# 1.net
KiCad netlist of a schematic drawn in Altium Designer
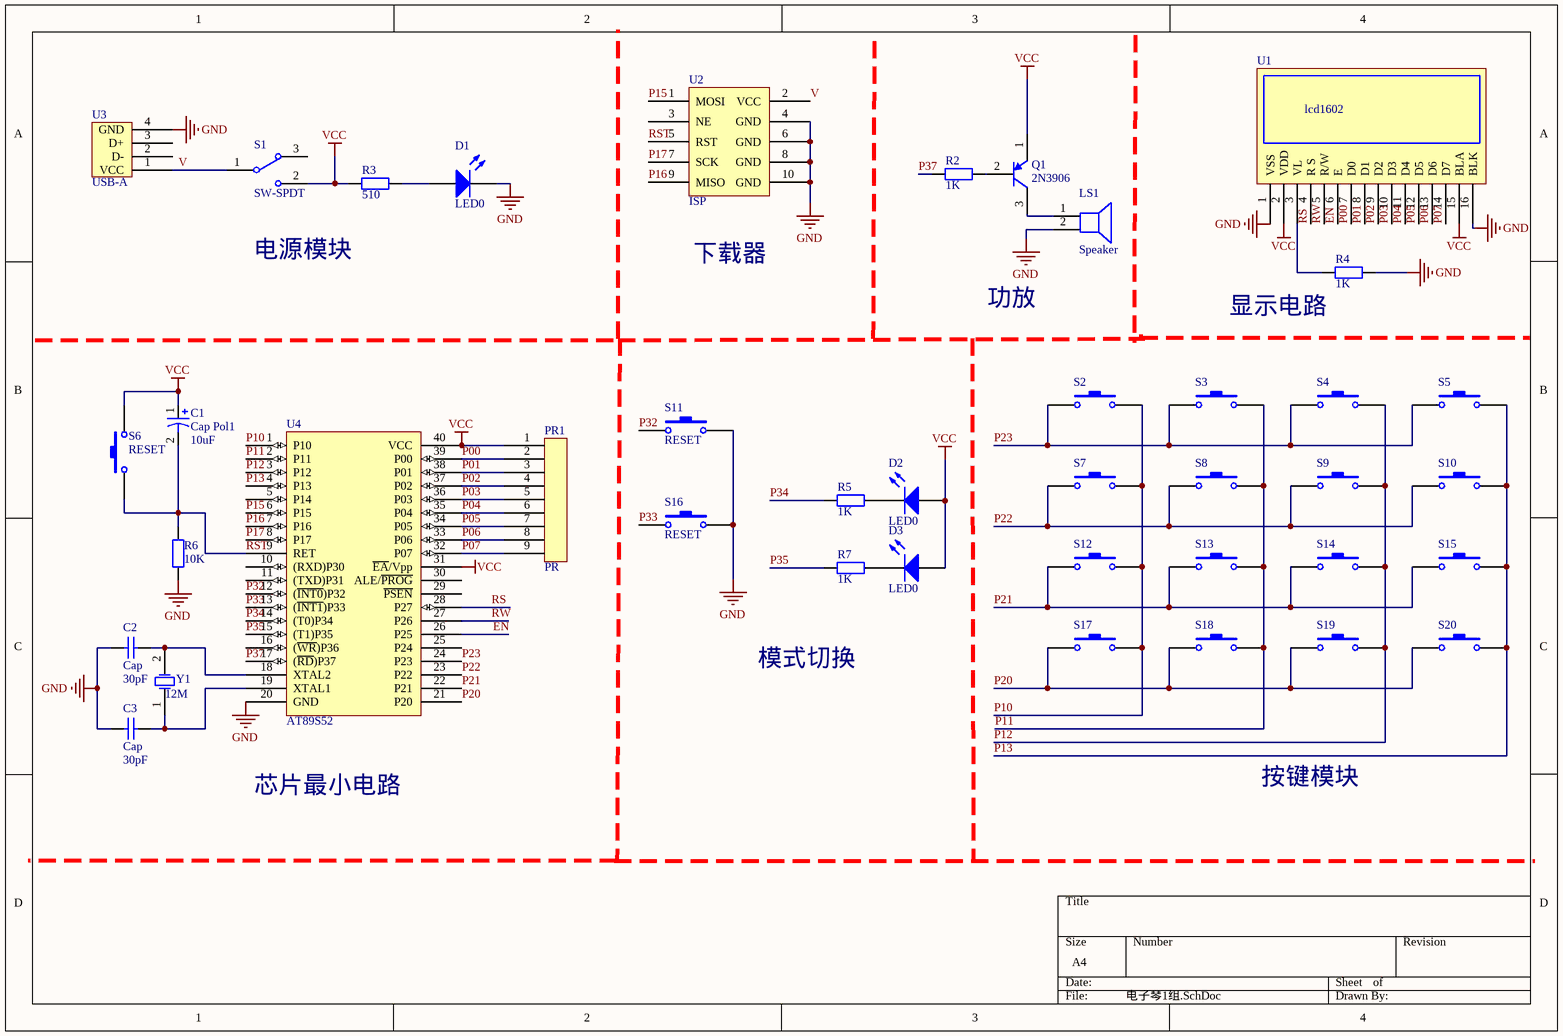
[diagram p0: 电子琴1组.SchDoc]

(export (version "E")
  (design (tool "Eeschema 10.0.6"))
  (components
    (comp (ref "C1")
      (value "Cap Pol1")
      (footprint "RB0.1")
      (description "Polarized Capacitor (Radial)")
      (fields (field (name "ALTIUM_VALUE") "10uF") (field (name "PUBLISHER") "Altium Limited"))
      (libsource (lib "schlib1-D") (part "Cap Pol1"))
    )
    (comp (ref "C2")
      (value "Cap")
      (footprint "RAD-0.1")
      (description "Capacitor")
      (fields (field (name "ALTIUM_VALUE") "30pF") (field (name "PUBLISHER") "Altium Limited"))
      (libsource (lib "schlib1-D") (part "Cap"))
    )
    (comp (ref "C3")
      (value "Cap")
      (footprint "RAD-0.1")
      (description "Capacitor")
      (fields (field (name "ALTIUM_VALUE") "30pF") (field (name "PUBLISHER") "Altium Limited"))
      (libsource (lib "schlib1-D") (part "Cap"))
    )
    (comp (ref "D1")
      (value "LED0")
      (footprint "RB0.1")
      (description "Typical INFRARED GaAs LED")
      (fields (field (name "PUBLISHER") "Altium Limited"))
      (libsource (lib "schlib1-D") (part "LED0"))
    )
    (comp (ref "D2")
      (value "LED0")
      (footprint "RB0.1")
      (description "Typical INFRARED GaAs LED")
      (fields (field (name "PUBLISHER") "Altium Limited"))
      (libsource (lib "schlib1-D") (part "LED0"))
    )
    (comp (ref "D3")
      (value "LED0")
      (footprint "RB0.1")
      (description "Typical INFRARED GaAs LED")
      (fields (field (name "PUBLISHER") "Altium Limited"))
      (libsource (lib "schlib1-D") (part "LED0"))
    )
    (comp (ref "LS1")
      (value "Speaker")
      (footprint "Speaker")
      (description "Loudspeaker")
      (fields (field (name "PUBLISHER") "Altium Limited"))
      (libsource (lib "schlib1-D") (part "Speaker"))
    )
    (comp (ref "PR1") (value "PR") (footprint "SIP9") (libsource (lib "Schlib1-4-22") (part "PR")))
    (comp (ref "Q1")
      (value "2N3906")
      (footprint "TO-92-M")
      (description "PNP General Purpose Amplifier")
      (fields (field (name "PUBLISHER") "Altium Limited"))
      (libsource (lib "schlib1-D") (part "2N3906"))
    )
    (comp (ref "R2")
      (value "1K")
      (footprint "AXIAL-0.3")
      (description "Resistor")
      (fields (field (name "PUBLISHER") "Altium Limited"))
      (libsource (lib "") (part "Res2_2"))
    )
    (comp (ref "R3")
      (value "510")
      (footprint "AXIAL-0.3")
      (description "Resistor")
      (fields (field (name "PUBLISHER") "Altium Limited"))
      (libsource (lib "schlib1-D") (part "Res2"))
    )
    (comp (ref "R4")
      (value "1K")
      (footprint "AXIAL-0.3")
      (description "Resistor")
      (fields (field (name "PUBLISHER") "Altium Limited"))
      (libsource (lib "schlib1-D") (part "Res2"))
    )
    (comp (ref "R5")
      (value "1K")
      (footprint "AXIAL-0.3")
      (description "Resistor")
      (fields (field (name "PUBLISHER") "Altium Limited"))
      (libsource (lib "schlib1-D") (part "Res2"))
    )
    (comp (ref "R6")
      (value "10K")
      (footprint "AXIAL-0.3")
      (description "Resistor")
      (fields (field (name "PUBLISHER") "Altium Limited"))
      (libsource (lib "") (part "Res2_1"))
    )
    (comp (ref "R7")
      (value "1K")
      (footprint "AXIAL-0.3")
      (description "Resistor")
      (fields (field (name "PUBLISHER") "Altium Limited"))
      (libsource (lib "schlib1-D") (part "Res2"))
    )
    (comp (ref "S1")
      (value "SW-SPDT")
      (footprint "KEY-6 - duplicate")
      (description "SPDT Subminiature Toggle Switch, Right Angle Mounting, Vertical Actuation")
      (fields (field (name "PUBLISHER") "Altium Limited"))
      (libsource (lib "schlib1-D") (part "SW-SPDT"))
    )
    (comp (ref "S2")
      (value "~")
      (footprint "SPST6*6")
      (description "Switch")
      (fields (field (name "PUBLISHER") "Altium Limited"))
      (libsource (lib "schlib1-D") (part "SW-PB"))
    )
    (comp (ref "S3")
      (value "~")
      (footprint "SPST6*6")
      (description "Switch")
      (fields (field (name "PUBLISHER") "Altium Limited"))
      (libsource (lib "schlib1-D") (part "SW-PB"))
    )
    (comp (ref "S4")
      (value "~")
      (footprint "SPST6*6")
      (description "Switch")
      (fields (field (name "PUBLISHER") "Altium Limited"))
      (libsource (lib "schlib1-D") (part "SW-PB"))
    )
    (comp (ref "S5")
      (value "~")
      (footprint "SPST6*6")
      (description "Switch")
      (fields (field (name "PUBLISHER") "Altium Limited"))
      (libsource (lib "schlib1-D") (part "SW-PB"))
    )
    (comp (ref "S6")
      (value "RESET")
      (footprint "SPST6*6")
      (description "Switch")
      (fields (field (name "PUBLISHER") "Altium Limited"))
      (libsource (lib "schlib1-D") (part "SW-PB"))
    )
    (comp (ref "S7")
      (value "~")
      (footprint "SPST6*6")
      (description "Switch")
      (fields (field (name "PUBLISHER") "Altium Limited"))
      (libsource (lib "schlib1-D") (part "SW-PB"))
    )
    (comp (ref "S8")
      (value "~")
      (footprint "SPST6*6")
      (description "Switch")
      (fields (field (name "PUBLISHER") "Altium Limited"))
      (libsource (lib "schlib1-D") (part "SW-PB"))
    )
    (comp (ref "S9")
      (value "~")
      (footprint "SPST6*6")
      (description "Switch")
      (fields (field (name "PUBLISHER") "Altium Limited"))
      (libsource (lib "schlib1-D") (part "SW-PB"))
    )
    (comp (ref "S10")
      (value "~")
      (footprint "SPST6*6")
      (description "Switch")
      (fields (field (name "PUBLISHER") "Altium Limited"))
      (libsource (lib "schlib1-D") (part "SW-PB"))
    )
    (comp (ref "S11")
      (value "RESET")
      (footprint "SPST6*6")
      (description "Switch")
      (fields (field (name "PUBLISHER") "Altium Limited"))
      (libsource (lib "schlib1-D") (part "SW-PB"))
    )
    (comp (ref "S12")
      (value "~")
      (footprint "SPST6*6")
      (description "Switch")
      (fields (field (name "PUBLISHER") "Altium Limited"))
      (libsource (lib "schlib1-D") (part "SW-PB"))
    )
    (comp (ref "S13")
      (value "~")
      (footprint "SPST6*6")
      (description "Switch")
      (fields (field (name "PUBLISHER") "Altium Limited"))
      (libsource (lib "schlib1-D") (part "SW-PB"))
    )
    (comp (ref "S14")
      (value "~")
      (footprint "SPST6*6")
      (description "Switch")
      (fields (field (name "PUBLISHER") "Altium Limited"))
      (libsource (lib "schlib1-D") (part "SW-PB"))
    )
    (comp (ref "S15")
      (value "~")
      (footprint "SPST6*6")
      (description "Switch")
      (fields (field (name "PUBLISHER") "Altium Limited"))
      (libsource (lib "schlib1-D") (part "SW-PB"))
    )
    (comp (ref "S16")
      (value "RESET")
      (footprint "SPST6*6")
      (description "Switch")
      (fields (field (name "PUBLISHER") "Altium Limited"))
      (libsource (lib "schlib1-D") (part "SW-PB"))
    )
    (comp (ref "S17")
      (value "~")
      (footprint "SPST6*6")
      (description "Switch")
      (fields (field (name "PUBLISHER") "Altium Limited"))
      (libsource (lib "schlib1-D") (part "SW-PB"))
    )
    (comp (ref "S18")
      (value "~")
      (footprint "SPST6*6")
      (description "Switch")
      (fields (field (name "PUBLISHER") "Altium Limited"))
      (libsource (lib "schlib1-D") (part "SW-PB"))
    )
    (comp (ref "S19")
      (value "~")
      (footprint "SPST6*6")
      (description "Switch")
      (fields (field (name "PUBLISHER") "Altium Limited"))
      (libsource (lib "schlib1-D") (part "SW-PB"))
    )
    (comp (ref "S20")
      (value "~")
      (footprint "SPST6*6")
      (description "Switch")
      (fields (field (name "PUBLISHER") "Altium Limited"))
      (libsource (lib "schlib1-D") (part "SW-PB"))
    )
    (comp (ref "U1")
      (value "lcd1602")
      (footprint "LCD1602")
      (libsource (lib "Schlib LED1206") (part "lcd1602"))
    )
    (comp (ref "U2") (value "ISP") (footprint "IDC10") (libsource (lib "Schlib1-4-22") (part "ISP")))
    (comp (ref "U3") (value "USB-A") (footprint "USB_A") (libsource (lib "Schlib1-4-22") (part "USB-A")))
    (comp (ref "U4")
      (value "AT89S52")
      (footprint "DIP40_51MCU")
      (libsource (lib "Schlib1-4-22") (part "AT89S52"))
    )
    (comp (ref "Y1")
      (value "12M")
      (footprint "XTAL1")
      (description "Crystal Oscillator")
      (fields (field (name "PUBLISHER") "Altium Limited"))
      (libsource (lib "schlib1-D") (part "XTAL"))
    )
  )
  (nets
    (net (code "1") (name "/EN") (class "Default")
      (node (ref "U1") (pin "6") (pinfunction "E_6") (pintype "passive"))
      (node (ref "U4") (pin "26") (pinfunction "P25_26") (pintype "passive"))
    )
    (net (code "2") (name "/P00") (class "Default")
      (node (ref "PR1") (pin "2") (pinfunction "1_2") (pintype "passive"))
      (node (ref "U1") (pin "7") (pinfunction "D0_7") (pintype "passive"))
      (node (ref "U4") (pin "39") (pinfunction "P00_39") (pintype "bidirectional"))
    )
    (net (code "3") (name "/P01") (class "Default")
      (node (ref "PR1") (pin "3") (pinfunction "2_3") (pintype "passive"))
      (node (ref "U1") (pin "8") (pinfunction "D1_8") (pintype "passive"))
      (node (ref "U4") (pin "38") (pinfunction "P01_38") (pintype "bidirectional"))
    )
    (net (code "4") (name "/P02") (class "Default")
      (node (ref "PR1") (pin "4") (pinfunction "4_4") (pintype "passive"))
      (node (ref "U1") (pin "9") (pinfunction "D2_9") (pintype "passive"))
      (node (ref "U4") (pin "37") (pinfunction "P02_37") (pintype "bidirectional"))
    )
    (net (code "5") (name "/P03") (class "Default")
      (node (ref "PR1") (pin "5") (pinfunction "5_5") (pintype "passive"))
      (node (ref "U1") (pin "10") (pinfunction "D3_10") (pintype "passive"))
      (node (ref "U4") (pin "36") (pinfunction "P03_36") (pintype "bidirectional"))
    )
    (net (code "6") (name "/P04") (class "Default")
      (node (ref "PR1") (pin "6") (pinfunction "6_6") (pintype "passive"))
      (node (ref "U1") (pin "11") (pinfunction "D4_11") (pintype "passive"))
      (node (ref "U4") (pin "35") (pinfunction "P04_35") (pintype "bidirectional"))
    )
    (net (code "7") (name "/P05") (class "Default")
      (node (ref "PR1") (pin "7") (pinfunction "7_7") (pintype "passive"))
      (node (ref "U1") (pin "12") (pinfunction "D5_12") (pintype "passive"))
      (node (ref "U4") (pin "34") (pinfunction "P05_34") (pintype "bidirectional"))
    )
    (net (code "8") (name "/P06") (class "Default")
      (node (ref "PR1") (pin "8") (pinfunction "8_8") (pintype "passive"))
      (node (ref "U1") (pin "13") (pinfunction "D6_13") (pintype "passive"))
      (node (ref "U4") (pin "33") (pinfunction "P06_33") (pintype "bidirectional"))
    )
    (net (code "9") (name "/P07") (class "Default")
      (node (ref "PR1") (pin "9") (pinfunction "9_9") (pintype "passive"))
      (node (ref "U1") (pin "14") (pinfunction "D7_14") (pintype "passive"))
      (node (ref "U4") (pin "32") (pinfunction "P07_32") (pintype "bidirectional"))
    )
    (net (code "10") (name "/P10") (class "Default")
      (node (ref "S12") (pin "2") (pinfunction "2_2") (pintype "passive"))
      (node (ref "S17") (pin "2") (pinfunction "2_2") (pintype "passive"))
      (node (ref "S2") (pin "2") (pinfunction "2_2") (pintype "passive"))
      (node (ref "S7") (pin "2") (pinfunction "2_2") (pintype "passive"))
      (node (ref "U4") (pin "1") (pinfunction "P10_1") (pintype "bidirectional"))
    )
    (net (code "11") (name "/P11") (class "Default")
      (node (ref "S13") (pin "2") (pinfunction "2_2") (pintype "passive"))
      (node (ref "S18") (pin "2") (pinfunction "2_2") (pintype "passive"))
      (node (ref "S3") (pin "2") (pinfunction "2_2") (pintype "passive"))
      (node (ref "S8") (pin "2") (pinfunction "2_2") (pintype "passive"))
      (node (ref "U4") (pin "2") (pinfunction "P11_2") (pintype "bidirectional"))
    )
    (net (code "12") (name "/P12") (class "Default")
      (node (ref "S14") (pin "2") (pinfunction "2_2") (pintype "passive"))
      (node (ref "S19") (pin "2") (pinfunction "2_2") (pintype "passive"))
      (node (ref "S4") (pin "2") (pinfunction "2_2") (pintype "passive"))
      (node (ref "S9") (pin "2") (pinfunction "2_2") (pintype "passive"))
      (node (ref "U4") (pin "3") (pinfunction "P12_3") (pintype "bidirectional"))
    )
    (net (code "13") (name "/P13") (class "Default")
      (node (ref "S10") (pin "2") (pinfunction "2_2") (pintype "passive"))
      (node (ref "S15") (pin "2") (pinfunction "2_2") (pintype "passive"))
      (node (ref "S20") (pin "2") (pinfunction "2_2") (pintype "passive"))
      (node (ref "S5") (pin "2") (pinfunction "2_2") (pintype "passive"))
      (node (ref "U4") (pin "4") (pinfunction "P13_4") (pintype "bidirectional"))
    )
    (net (code "14") (name "/P15") (class "Default")
      (node (ref "U2") (pin "1") (pinfunction "MOSI_1") (pintype "passive"))
      (node (ref "U4") (pin "6") (pinfunction "P15_6") (pintype "bidirectional"))
    )
    (net (code "15") (name "/P16") (class "Default")
      (node (ref "U2") (pin "9") (pinfunction "MISO_9") (pintype "passive"))
      (node (ref "U4") (pin "7") (pinfunction "P16_7") (pintype "bidirectional"))
    )
    (net (code "16") (name "/P17") (class "Default")
      (node (ref "U2") (pin "7") (pinfunction "SCK_7") (pintype "passive"))
      (node (ref "U4") (pin "8") (pinfunction "P17_8") (pintype "bidirectional"))
    )
    (net (code "17") (name "/P20") (class "Default")
      (node (ref "S17") (pin "1") (pinfunction "1_1") (pintype "passive"))
      (node (ref "S18") (pin "1") (pinfunction "1_1") (pintype "passive"))
      (node (ref "S19") (pin "1") (pinfunction "1_1") (pintype "passive"))
      (node (ref "S20") (pin "1") (pinfunction "1_1") (pintype "passive"))
      (node (ref "U4") (pin "21") (pinfunction "P20_21") (pintype "passive"))
    )
    (net (code "18") (name "/P21") (class "Default")
      (node (ref "S12") (pin "1") (pinfunction "1_1") (pintype "passive"))
      (node (ref "S13") (pin "1") (pinfunction "1_1") (pintype "passive"))
      (node (ref "S14") (pin "1") (pinfunction "1_1") (pintype "passive"))
      (node (ref "S15") (pin "1") (pinfunction "1_1") (pintype "passive"))
      (node (ref "U4") (pin "22") (pinfunction "P21_22") (pintype "passive"))
    )
    (net (code "19") (name "/P22") (class "Default")
      (node (ref "S10") (pin "1") (pinfunction "1_1") (pintype "passive"))
      (node (ref "S7") (pin "1") (pinfunction "1_1") (pintype "passive"))
      (node (ref "S8") (pin "1") (pinfunction "1_1") (pintype "passive"))
      (node (ref "S9") (pin "1") (pinfunction "1_1") (pintype "passive"))
      (node (ref "U4") (pin "23") (pinfunction "P22_23") (pintype "passive"))
    )
    (net (code "20") (name "/P23") (class "Default")
      (node (ref "S2") (pin "1") (pinfunction "1_1") (pintype "passive"))
      (node (ref "S3") (pin "1") (pinfunction "1_1") (pintype "passive"))
      (node (ref "S4") (pin "1") (pinfunction "1_1") (pintype "passive"))
      (node (ref "S5") (pin "1") (pinfunction "1_1") (pintype "passive"))
      (node (ref "U4") (pin "24") (pinfunction "P23_24") (pintype "passive"))
    )
    (net (code "21") (name "/P32") (class "Default")
      (node (ref "S11") (pin "1") (pinfunction "1_1") (pintype "passive"))
      (node (ref "U4") (pin "12") (pinfunction "(~{INT0})P32_12") (pintype "bidirectional"))
    )
    (net (code "22") (name "/P33") (class "Default")
      (node (ref "S16") (pin "1") (pinfunction "1_1") (pintype "passive"))
      (node (ref "U4") (pin "13") (pinfunction "(~{INT1})P33_13") (pintype "bidirectional"))
    )
    (net (code "23") (name "/P34") (class "Default")
      (node (ref "R5") (pin "1") (pinfunction "1_1") (pintype "passive"))
      (node (ref "U4") (pin "14") (pinfunction "(T0)P34_14") (pintype "bidirectional"))
    )
    (net (code "24") (name "/P35") (class "Default")
      (node (ref "R7") (pin "1") (pinfunction "1_1") (pintype "passive"))
      (node (ref "U4") (pin "15") (pinfunction "(T1)P35_15") (pintype "bidirectional"))
    )
    (net (code "25") (name "/P37") (class "Default")
      (node (ref "R2") (pin "2") (pinfunction "2_2") (pintype "passive"))
      (node (ref "U4") (pin "17") (pinfunction "(~{RD})P37_17") (pintype "bidirectional"))
    )
    (net (code "26") (name "/RS") (class "Default")
      (node (ref "U1") (pin "4") (pinfunction "R_S_4") (pintype "passive"))
      (node (ref "U4") (pin "28") (pinfunction "P27_28") (pintype "bidirectional"))
    )
    (net (code "27") (name "/RST") (class "Default")
      (node (ref "C1") (pin "2") (pinfunction "2_2") (pintype "passive"))
      (node (ref "R6") (pin "2") (pinfunction "2_2") (pintype "passive"))
      (node (ref "S6") (pin "1") (pinfunction "1_1") (pintype "passive"))
      (node (ref "U2") (pin "5") (pinfunction "RST_5") (pintype "passive"))
      (node (ref "U4") (pin "9") (pinfunction "RET_9") (pintype "passive"))
    )
    (net (code "28") (name "/RW") (class "Default")
      (node (ref "U1") (pin "5") (pinfunction "R/W_5") (pintype "passive"))
      (node (ref "U4") (pin "27") (pinfunction "P26_27") (pintype "passive"))
    )
    (net (code "29") (name "/V") (class "Default")
      (node (ref "S1") (pin "1") (pinfunction "2_1") (pintype "passive"))
      (node (ref "U2") (pin "2") (pinfunction "VCC_2") (pintype "passive"))
      (node (ref "U3") (pin "1") (pinfunction "VCC_1") (pintype "passive"))
    )
    (net (code "30") (name "GND") (class "Default")
      (node (ref "C2") (pin "1") (pinfunction "1_1") (pintype "passive"))
      (node (ref "C3") (pin "1") (pinfunction "1_1") (pintype "passive"))
      (node (ref "D1") (pin "2") (pinfunction "K_2") (pintype "passive"))
      (node (ref "LS1") (pin "2") (pinfunction "2_2") (pintype "passive"))
      (node (ref "R4") (pin "2") (pinfunction "2_2") (pintype "passive"))
      (node (ref "R6") (pin "1") (pinfunction "1_1") (pintype "passive"))
      (node (ref "S11") (pin "2") (pinfunction "2_2") (pintype "passive"))
      (node (ref "S16") (pin "2") (pinfunction "2_2") (pintype "passive"))
      (node (ref "U1") (pin "1") (pinfunction "VSS_1") (pintype "passive"))
      (node (ref "U1") (pin "16") (pinfunction "BLK_16") (pintype "passive"))
      (node (ref "U2") (pin "10") (pinfunction "GND_10") (pintype "passive"))
      (node (ref "U2") (pin "4") (pinfunction "GND_4") (pintype "passive"))
      (node (ref "U2") (pin "6") (pinfunction "GND_6") (pintype "passive"))
      (node (ref "U2") (pin "8") (pinfunction "GND_8") (pintype "passive"))
      (node (ref "U3") (pin "4") (pinfunction "GND_4") (pintype "passive"))
      (node (ref "U4") (pin "20") (pinfunction "GND_20") (pintype "passive"))
    )
    (net (code "31") (name "Net-(D1-A)") (class "Default")
      (node (ref "D1") (pin "1") (pinfunction "A_1") (pintype "passive"))
      (node (ref "R3") (pin "2") (pinfunction "2_2") (pintype "passive"))
    )
    (net (code "32") (name "Net-(D2-K)") (class "Default")
      (node (ref "D2") (pin "2") (pinfunction "K_2") (pintype "passive"))
      (node (ref "R5") (pin "2") (pinfunction "2_2") (pintype "passive"))
    )
    (net (code "33") (name "Net-(D3-K)") (class "Default")
      (node (ref "D3") (pin "2") (pinfunction "K_2") (pintype "passive"))
      (node (ref "R7") (pin "2") (pinfunction "2_2") (pintype "passive"))
    )
    (net (code "34") (name "Net-(Q1-B)") (class "Default")
      (node (ref "Q1") (pin "2") (pinfunction "B_2") (pintype "passive"))
      (node (ref "R2") (pin "1") (pinfunction "1_1") (pintype "passive"))
    )
    (net (code "35") (name "Net-(Q1-C)") (class "Default")
      (node (ref "LS1") (pin "1") (pinfunction "1_1") (pintype "passive"))
      (node (ref "Q1") (pin "3") (pinfunction "C_3") (pintype "passive"))
    )
    (net (code "36") (name "Net-(U1-VL)") (class "Default")
      (node (ref "R4") (pin "1") (pinfunction "1_1") (pintype "passive"))
      (node (ref "U1") (pin "3") (pinfunction "VL_3") (pintype "passive"))
    )
    (net (code "37") (name "Net-(U4-XTAL1)") (class "Default")
      (node (ref "C3") (pin "2") (pinfunction "2_2") (pintype "passive"))
      (node (ref "U4") (pin "19") (pinfunction "XTAL1_19") (pintype "passive"))
      (node (ref "Y1") (pin "1") (pinfunction "OSC1_1") (pintype "passive"))
    )
    (net (code "38") (name "Net-(U4-XTAL2)") (class "Default")
      (node (ref "C2") (pin "2") (pinfunction "2_2") (pintype "passive"))
      (node (ref "U4") (pin "18") (pinfunction "XTAL2_18") (pintype "passive"))
      (node (ref "Y1") (pin "2") (pinfunction "OSC2_2") (pintype "passive"))
    )
    (net (code "39") (name "VCC") (class "Default")
      (node (ref "C1") (pin "1") (pinfunction "1_1") (pintype "passive"))
      (node (ref "D2") (pin "1") (pinfunction "A_1") (pintype "passive"))
      (node (ref "D3") (pin "1") (pinfunction "A_1") (pintype "passive"))
      (node (ref "PR1") (pin "1") (pinfunction "0_1") (pintype "passive"))
      (node (ref "Q1") (pin "1") (pinfunction "E_1") (pintype "passive"))
      (node (ref "R3") (pin "1") (pinfunction "1_1") (pintype "passive"))
      (node (ref "S1") (pin "2") (pinfunction "1_2") (pintype "passive"))
      (node (ref "S6") (pin "2") (pinfunction "2_2") (pintype "passive"))
      (node (ref "U1") (pin "15") (pinfunction "BLA_15") (pintype "passive"))
      (node (ref "U1") (pin "2") (pinfunction "VDD_2") (pintype "passive"))
      (node (ref "U4") (pin "31") (pinfunction "~{EA}/Vpp_31") (pintype "passive"))
      (node (ref "U4") (pin "40") (pinfunction "VCC_40") (pintype "power_in"))
    )
    (net (code "40") (name "unconnected-(S1-Pad3)") (class "Default")
      (node (ref "S1") (pin "3") (pinfunction "3_3") (pintype "passive"))
    )
    (net (code "41") (name "unconnected-(U2-NE-Pad3)") (class "Default")
      (node (ref "U2") (pin "3") (pinfunction "NE_3") (pintype "passive"))
    )
    (net (code "42") (name "unconnected-(U3-D+-Pad3)") (class "Default")
      (node (ref "U3") (pin "3") (pinfunction "D+_3") (pintype "passive"))
    )
    (net (code "43") (name "unconnected-(U3-D--Pad2)") (class "Default")
      (node (ref "U3") (pin "2") (pinfunction "D-_2") (pintype "passive"))
    )
    (net (code "44") (name "unconnected-(U4-(RXD)P30-Pad10)") (class "Default")
      (node (ref "U4") (pin "10") (pinfunction "(RXD)P30_10") (pintype "bidirectional"))
    )
    (net (code "45") (name "unconnected-(U4-(TXD)P31-Pad11)") (class "Default")
      (node (ref "U4") (pin "11") (pinfunction "(TXD)P31_11") (pintype "bidirectional"))
    )
    (net (code "46") (name "unconnected-(U4-(~{WR})P36-Pad16)") (class "Default")
      (node (ref "U4") (pin "16") (pinfunction "(~{WR})P36_16") (pintype "bidirectional"))
    )
    (net (code "47") (name "unconnected-(U4-ALE{slash}~{PROG}-Pad30)") (class "Default")
      (node (ref "U4") (pin "30") (pinfunction "ALE/~{PROG}_30") (pintype "passive"))
    )
    (net (code "48") (name "unconnected-(U4-P14-Pad5)") (class "Default")
      (node (ref "U4") (pin "5") (pinfunction "P14_5") (pintype "bidirectional"))
    )
    (net (code "49") (name "unconnected-(U4-P24-Pad25)") (class "Default")
      (node (ref "U4") (pin "25") (pinfunction "P24_25") (pintype "passive"))
    )
    (net (code "50") (name "unconnected-(U4-~{PSEN}-Pad29)") (class "Default")
      (node (ref "U4") (pin "29") (pinfunction "~{PSEN}_29") (pintype "passive"))
    )
  )
)
